# TxPCB_V1-1_LR.net
KiCad netlist of a schematic drawn in EAGLE
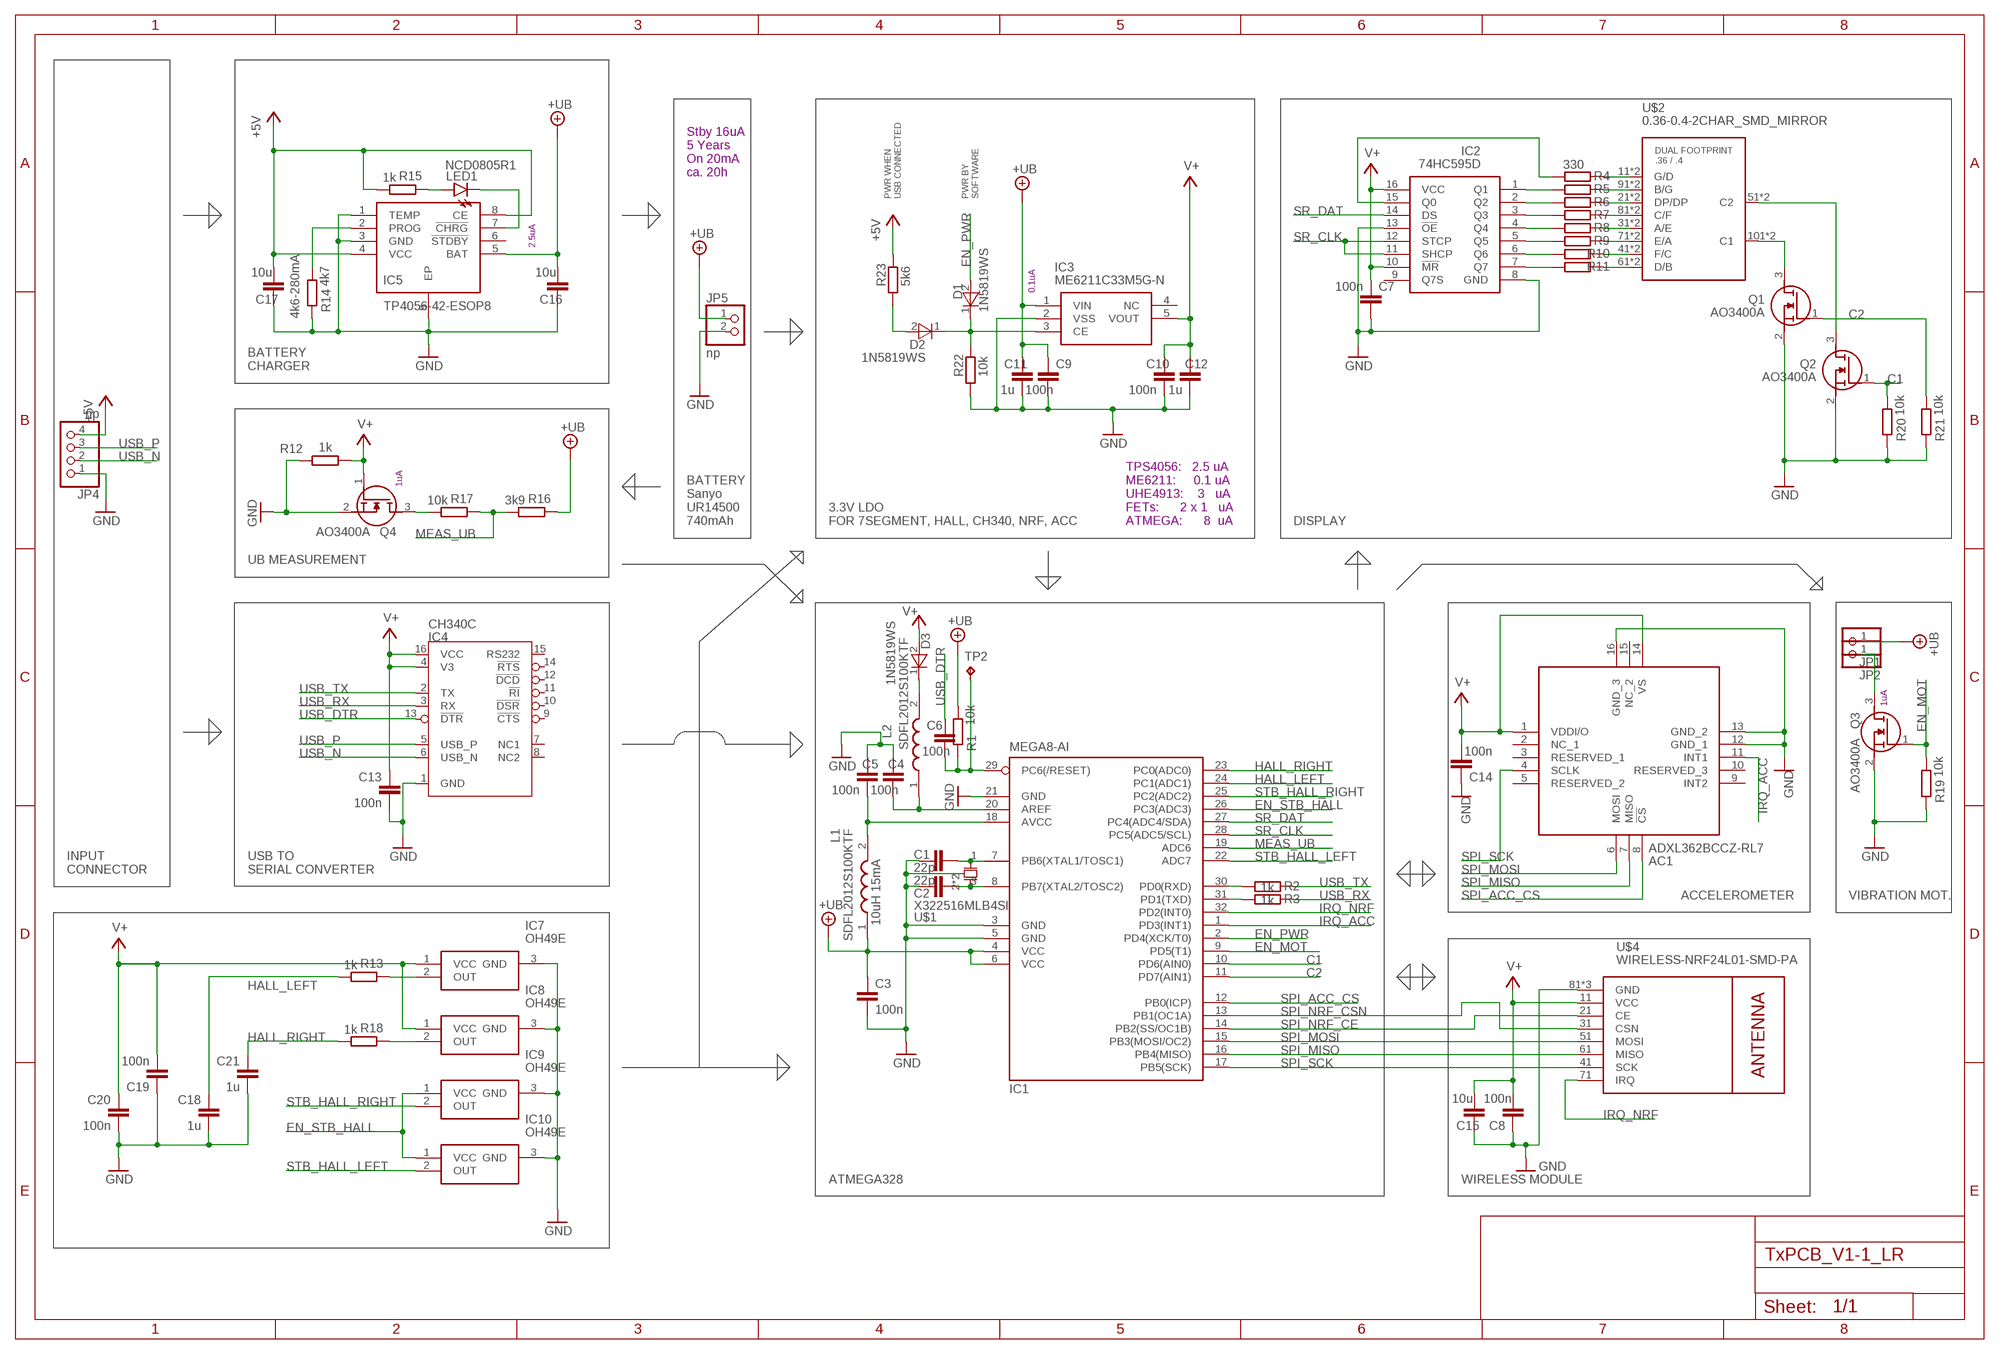
[diagram p0: schematic, sheet 1]

(export (version "E")
  (design (tool "Eeschema 10.0.6"))
  (components
    (comp (ref "AC1")
      (value "ADXL362BCCZ-RL7")
      (footprint "eagle-import:CC-16-4")
      (fields (field (name "MOUSER_PART_NUMBER") "584-ADXL362BCCZ-R7"))
      (libsource (lib "eagle-import") (part "ADXL362BCCZ-RL7"))
    )
    (comp (ref "C1")
      (value "22p")
      (footprint "eagle-import:C0603")
      (libsource (lib "eagle-import") (part "C-EUC0603"))
    )
    (comp (ref "C2")
      (value "22p")
      (footprint "eagle-import:C0603")
      (libsource (lib "eagle-import") (part "C-EUC0603"))
    )
    (comp (ref "C3")
      (value "100n")
      (footprint "eagle-import:C0603")
      (libsource (lib "eagle-import") (part "C-EUC0603"))
    )
    (comp (ref "C4")
      (value "100n")
      (footprint "eagle-import:C0603")
      (libsource (lib "eagle-import") (part "C-EUC0603"))
    )
    (comp (ref "C5")
      (value "100n")
      (footprint "eagle-import:C0603")
      (libsource (lib "eagle-import") (part "C-EUC0603"))
    )
    (comp (ref "C6")
      (value "100n")
      (footprint "eagle-import:C0603")
      (libsource (lib "eagle-import") (part "C-EUC0603"))
    )
    (comp (ref "C7")
      (value "100n")
      (footprint "eagle-import:C0603")
      (libsource (lib "eagle-import") (part "C-EUC0603"))
    )
    (comp (ref "C8")
      (value "100n")
      (footprint "eagle-import:C0603")
      (libsource (lib "eagle-import") (part "C-EUC0603"))
    )
    (comp (ref "C9")
      (value "100n")
      (footprint "eagle-import:C0603")
      (libsource (lib "eagle-import") (part "C-EUC0603"))
    )
    (comp (ref "C10")
      (value "100n")
      (footprint "eagle-import:C0603")
      (libsource (lib "eagle-import") (part "C-EUC0603"))
    )
    (comp (ref "C11")
      (value "1u")
      (footprint "eagle-import:C0603")
      (libsource (lib "eagle-import") (part "C-EUC0603"))
    )
    (comp (ref "C12")
      (value "1u")
      (footprint "eagle-import:C0603")
      (libsource (lib "eagle-import") (part "C-EUC0603"))
    )
    (comp (ref "C13")
      (value "100n")
      (footprint "eagle-import:C0603")
      (libsource (lib "eagle-import") (part "C-EUC0603"))
    )
    (comp (ref "C14")
      (value "100n")
      (footprint "eagle-import:C0603")
      (libsource (lib "eagle-import") (part "C-EUC0603"))
    )
    (comp (ref "C15")
      (value "10u")
      (footprint "eagle-import:C0603")
      (libsource (lib "eagle-import") (part "C-EUC0603"))
    )
    (comp (ref "C16")
      (value "10u")
      (footprint "eagle-import:C0603")
      (libsource (lib "eagle-import") (part "C-EUC0603"))
    )
    (comp (ref "C17")
      (value "10u")
      (footprint "eagle-import:C0603")
      (libsource (lib "eagle-import") (part "C-EUC0603"))
    )
    (comp (ref "C18")
      (value "1u")
      (footprint "eagle-import:C0603")
      (libsource (lib "eagle-import") (part "C-EUC0603"))
    )
    (comp (ref "C19")
      (value "100n")
      (footprint "eagle-import:C0603")
      (libsource (lib "eagle-import") (part "C-EUC0603"))
    )
    (comp (ref "C20")
      (value "100n")
      (footprint "eagle-import:C0603")
      (libsource (lib "eagle-import") (part "C-EUC0603"))
    )
    (comp (ref "C21")
      (value "1u")
      (footprint "eagle-import:C0603")
      (libsource (lib "eagle-import") (part "C-EUC0603"))
    )
    (comp (ref "D1")
      (value "1N5819WS")
      (footprint "eagle-import:SODFL2512X90N")
      (fields
        (field (name "ARROW_PART_NUMBER") "1N4148WS")
        (field (name "MOUSER_PART_NUMBER") "512-1N4148WS")
      )
      (libsource (lib "eagle-import") (part "1N4148WS"))
    )
    (comp (ref "D2")
      (value "1N5819WS")
      (footprint "eagle-import:SODFL2512X90N")
      (fields
        (field (name "ARROW_PART_NUMBER") "1N4148WS")
        (field (name "MOUSER_PART_NUMBER") "512-1N4148WS")
      )
      (libsource (lib "eagle-import") (part "1N4148WS"))
    )
    (comp (ref "D3")
      (value "1N5819WS")
      (footprint "eagle-import:SODFL2512X90N")
      (fields
        (field (name "ARROW_PART_NUMBER") "1N4148WS")
        (field (name "MOUSER_PART_NUMBER") "512-1N4148WS")
      )
      (libsource (lib "eagle-import") (part "1N4148WS"))
    )
    (comp (ref "IC1")
      (value "MEGA8-AI")
      (footprint "eagle-import:TQFP32-08")
      (fields (field (name "MPN") "ATMEGA8-16AU"))
      (libsource (lib "eagle-import") (part "MEGA8-AI"))
    )
    (comp (ref "IC2")
      (value "74HC595D")
      (footprint "eagle-import:SOIC127P600X175-16N")
      (libsource (lib "eagle-import") (part "74HC595D"))
    )
    (comp (ref "IC3")
      (value "ME6211C33M5G-N")
      (footprint "eagle-import:SOT95P282X145-5N")
      (fields (field (name "MANUFACTURER_PART_NUMBER") "ME6211C50M5G"))
      (libsource (lib "eagle-import") (part "ME6211C50M5G"))
    )
    (comp (ref "IC4")
      (value "CH340C")
      (footprint "eagle-import:SOIC16N")
      (libsource (lib "eagle-import") (part "CH340G"))
    )
    (comp (ref "IC5")
      (value "TP4056-42-ESOP8")
      (footprint "eagle-import:SOIC127P600X175-9N")
      (libsource (lib "eagle-import") (part "TP4056-42-ESOP8"))
    )
    (comp (ref "IC7")
      (value "OH49E")
      (footprint "eagle-import:SOT95P237X112-3N")
      (fields
        (field (name "ARROW_PART_NUMBER") "DRV5055A3QDBZR")
        (field (name "MOUSER_PART_NUMBER") "595-DRV5055A3QDBZR")
      )
      (libsource (lib "eagle-import") (part "DRV5055A3QDBZR"))
    )
    (comp (ref "IC8")
      (value "OH49E")
      (footprint "eagle-import:SOT95P237X112-3N")
      (fields
        (field (name "ARROW_PART_NUMBER") "DRV5055A3QDBZR")
        (field (name "MOUSER_PART_NUMBER") "595-DRV5055A3QDBZR")
      )
      (libsource (lib "eagle-import") (part "DRV5055A3QDBZR"))
    )
    (comp (ref "IC9")
      (value "OH49E")
      (footprint "eagle-import:SOT95P237X112-3N")
      (fields
        (field (name "ARROW_PART_NUMBER") "DRV5055A3QDBZR")
        (field (name "MOUSER_PART_NUMBER") "595-DRV5055A3QDBZR")
      )
      (libsource (lib "eagle-import") (part "DRV5055A3QDBZR"))
    )
    (comp (ref "IC10")
      (value "OH49E")
      (footprint "eagle-import:SOT95P237X112-3N")
      (fields
        (field (name "ARROW_PART_NUMBER") "DRV5055A3QDBZR")
        (field (name "MOUSER_PART_NUMBER") "595-DRV5055A3QDBZR")
      )
      (libsource (lib "eagle-import") (part "DRV5055A3QDBZR"))
    )
    (comp (ref "JP1")
      (value "PINHD-1X1")
      (footprint "eagle-import:1X01")
      (libsource (lib "eagle-import") (part "PINHD-1X1"))
    )
    (comp (ref "JP2")
      (value "PINHD-1X1")
      (footprint "eagle-import:1X01")
      (libsource (lib "eagle-import") (part "PINHD-1X1"))
    )
    (comp (ref "JP4")
      (value "np")
      (footprint "eagle-import:1X04")
      (libsource (lib "eagle-import") (part "PINHD-1X4"))
    )
    (comp (ref "JP5")
      (value "np")
      (footprint "eagle-import:1X02")
      (libsource (lib "eagle-import") (part "PINHD-1X2"))
    )
    (comp (ref "L1")
      (value "SDFL2012S100KTF")
      (footprint "eagle-import:INDC2112X105N")
      (fields (field (name "MANUFACTURER_PART_NUMBER") "SDFL2012Q2R7KTF"))
      (libsource (lib "eagle-import") (part "SDFL2012Q2R7KTF"))
    )
    (comp (ref "L2")
      (value "SDFL2012S100KTF")
      (footprint "eagle-import:INDC2112X105N")
      (fields (field (name "MANUFACTURER_PART_NUMBER") "SDFL2012Q2R7KTF"))
      (libsource (lib "eagle-import") (part "SDFL2012Q2R7KTF"))
    )
    (comp (ref "LED1")
      (value "NCD0805R1")
      (footprint "eagle-import:CHIP-LED0805")
      (libsource (lib "eagle-import") (part "LEDCHIP-LED0805"))
    )
    (comp (ref "Q1")
      (value "AO3400A")
      (footprint "eagle-import:SOT95P280X125-3N")
      (libsource (lib "eagle-import") (part "AO3400A"))
    )
    (comp (ref "Q2")
      (value "AO3400A")
      (footprint "eagle-import:SOT95P280X125-3N")
      (libsource (lib "eagle-import") (part "AO3400A"))
    )
    (comp (ref "Q3")
      (value "AO3400A")
      (footprint "eagle-import:SOT95P280X125-3N")
      (libsource (lib "eagle-import") (part "AO3400A"))
    )
    (comp (ref "Q4")
      (value "AO3400A")
      (footprint "eagle-import:SOT95P280X125-3N")
      (libsource (lib "eagle-import") (part "AO3400A"))
    )
    (comp (ref "R1")
      (value "10k")
      (footprint "eagle-import:R0603")
      (libsource (lib "eagle-import") (part "R-EU_R0603"))
    )
    (comp (ref "R2")
      (value "1k")
      (footprint "eagle-import:R0603")
      (libsource (lib "eagle-import") (part "R-EU_R0603"))
    )
    (comp (ref "R3")
      (value "1k")
      (footprint "eagle-import:R0603")
      (libsource (lib "eagle-import") (part "R-EU_R0603"))
    )
    (comp (ref "R4")
      (value "330")
      (footprint "eagle-import:R0603")
      (libsource (lib "eagle-import") (part "R-EU_R0603"))
    )
    (comp (ref "R5")
      (value "330")
      (footprint "eagle-import:R0603")
      (libsource (lib "eagle-import") (part "R-EU_R0603"))
    )
    (comp (ref "R6")
      (value "330")
      (footprint "eagle-import:R0603")
      (libsource (lib "eagle-import") (part "R-EU_R0603"))
    )
    (comp (ref "R7")
      (value "330")
      (footprint "eagle-import:R0603")
      (libsource (lib "eagle-import") (part "R-EU_R0603"))
    )
    (comp (ref "R8")
      (value "330")
      (footprint "eagle-import:R0603")
      (libsource (lib "eagle-import") (part "R-EU_R0603"))
    )
    (comp (ref "R9")
      (value "330")
      (footprint "eagle-import:R0603")
      (libsource (lib "eagle-import") (part "R-EU_R0603"))
    )
    (comp (ref "R10")
      (value "330")
      (footprint "eagle-import:R0603")
      (libsource (lib "eagle-import") (part "R-EU_R0603"))
    )
    (comp (ref "R11")
      (value "330")
      (footprint "eagle-import:R0603")
      (libsource (lib "eagle-import") (part "R-EU_R0603"))
    )
    (comp (ref "R12")
      (value "1k")
      (footprint "eagle-import:R0603")
      (libsource (lib "eagle-import") (part "R-EU_R0603"))
    )
    (comp (ref "R13")
      (value "1k")
      (footprint "eagle-import:R0603")
      (libsource (lib "eagle-import") (part "R-EU_R0603"))
    )
    (comp (ref "R14")
      (value "4k7")
      (footprint "eagle-import:R0603")
      (libsource (lib "eagle-import") (part "R-EU_R0603"))
    )
    (comp (ref "R15")
      (value "1k")
      (footprint "eagle-import:R0603")
      (libsource (lib "eagle-import") (part "R-EU_R0603"))
    )
    (comp (ref "R16")
      (value "3k9")
      (footprint "eagle-import:R0603")
      (libsource (lib "eagle-import") (part "R-EU_R0603"))
    )
    (comp (ref "R17")
      (value "10k")
      (footprint "eagle-import:R0603")
      (libsource (lib "eagle-import") (part "R-EU_R0603"))
    )
    (comp (ref "R18")
      (value "1k")
      (footprint "eagle-import:R0603")
      (libsource (lib "eagle-import") (part "R-EU_R0603"))
    )
    (comp (ref "R19")
      (value "10k")
      (footprint "eagle-import:R0603")
      (libsource (lib "eagle-import") (part "R-EU_R0603"))
    )
    (comp (ref "R20")
      (value "10k")
      (footprint "eagle-import:R0603")
      (libsource (lib "eagle-import") (part "R-EU_R0603"))
    )
    (comp (ref "R21")
      (value "10k")
      (footprint "eagle-import:R0603")
      (libsource (lib "eagle-import") (part "R-EU_R0603"))
    )
    (comp (ref "R22")
      (value "10k")
      (footprint "eagle-import:R0603")
      (libsource (lib "eagle-import") (part "R-EU_R0603"))
    )
    (comp (ref "R23")
      (value "5k6")
      (footprint "eagle-import:R0603")
      (libsource (lib "eagle-import") (part "R-EU_R0603"))
    )
    (comp (ref "TP2")
      (value "TPB1,27")
      (footprint "eagle-import:B1,27")
      (libsource (lib "eagle-import") (part "TPB1,27"))
    )
    (comp (ref "U$1")
      (value "X322516MLB4SI")
      (footprint "eagle-import:X322516MLB4SI")
      (libsource (lib "eagle-import") (part "X322516_BETTER"))
    )
    (comp (ref "U$2")
      (value "0.36-0.4-2CHAR_SMD_MIRROR")
      (footprint "eagle-import:COMBO-036-04_SMD")
      (libsource (lib "eagle-import") (part "0.36-0.4-2CHAR_SMD_MIRROR"))
    )
    (comp (ref "U$4")
      (value "WIRELESS-NRF24L01-SMD-PA")
      (footprint "eagle-import:WIRELESS-NRF24L01_SMD_PA")
      (libsource (lib "eagle-import") (part "WIRELESS-NRF24L01-SMD-PA"))
    )
  )
  (nets
    (net (code "1") (name "+5V") (class "Default")
      (node (ref "C17") (pin "1") (pinfunction "1_1") (pintype "passive"))
      (node (ref "IC5") (pin "4") (pinfunction "VCC_4") (pintype "bidirectional"))
      (node (ref "IC5") (pin "8") (pinfunction "CE_8") (pintype "bidirectional"))
      (node (ref "JP4") (pin "4") (pinfunction "4_4") (pintype "passive"))
      (node (ref "R15") (pin "2") (pinfunction "2_2") (pintype "passive"))
      (node (ref "R23") (pin "2") (pinfunction "2_2") (pintype "passive"))
    )
    (net (code "2") (name "+UB") (class "Default")
      (node (ref "C11") (pin "1") (pinfunction "1_1") (pintype "passive"))
      (node (ref "C16") (pin "1") (pinfunction "1_1") (pintype "passive"))
      (node (ref "C3") (pin "1") (pinfunction "1_1") (pintype "passive"))
      (node (ref "C9") (pin "1") (pinfunction "1_1") (pintype "passive"))
      (node (ref "IC1") (pin "4") (pinfunction "VCC_4") (pintype "power_in"))
      (node (ref "IC1") (pin "6") (pinfunction "VCC_6") (pintype "power_in"))
      (node (ref "IC3") (pin "1") (pinfunction "VIN_1") (pintype "bidirectional"))
      (node (ref "IC5") (pin "5") (pinfunction "BAT_5") (pintype "bidirectional"))
      (node (ref "JP1") (pin "1") (pinfunction "1_1") (pintype "passive"))
      (node (ref "JP5") (pin "1") (pinfunction "1_1") (pintype "passive"))
      (node (ref "L1") (pin "1") (pinfunction "1_1") (pintype "bidirectional"))
      (node (ref "R1") (pin "2") (pinfunction "2_2") (pintype "passive"))
      (node (ref "R16") (pin "1") (pinfunction "1_1") (pintype "passive"))
    )
    (net (code "3") (name "/C1") (class "Default")
      (node (ref "IC1") (pin "10") (pinfunction "PD6(AIN0)_10") (pintype "bidirectional"))
      (node (ref "Q2") (pin "1") (pinfunction "G_1") (pintype "bidirectional"))
      (node (ref "R20") (pin "2") (pinfunction "2_2") (pintype "passive"))
    )
    (net (code "4") (name "/C2") (class "Default")
      (node (ref "IC1") (pin "11") (pinfunction "PD7(AIN1)_11") (pintype "bidirectional"))
      (node (ref "Q1") (pin "1") (pinfunction "G_1") (pintype "bidirectional"))
      (node (ref "R21") (pin "2") (pinfunction "2_2") (pintype "passive"))
    )
    (net (code "5") (name "/EN_MOT") (class "Default")
      (node (ref "IC1") (pin "9") (pinfunction "PD5(T1)_9") (pintype "bidirectional"))
      (node (ref "Q3") (pin "1") (pinfunction "G_1") (pintype "bidirectional"))
      (node (ref "R19") (pin "2") (pinfunction "2_2") (pintype "passive"))
    )
    (net (code "6") (name "/EN_PWR") (class "Default")
      (node (ref "D1") (pin "2") (pinfunction "A_2") (pintype "bidirectional"))
      (node (ref "IC1") (pin "2") (pinfunction "PD4(XCK/T0)_2") (pintype "bidirectional"))
    )
    (net (code "7") (name "/EN_STB_HALL") (class "Default")
      (node (ref "IC1") (pin "26") (pinfunction "PC3(ADC3)_26") (pintype "bidirectional"))
      (node (ref "IC10") (pin "1") (pinfunction "VCC_1") (pintype "bidirectional"))
      (node (ref "IC9") (pin "1") (pinfunction "VCC_1") (pintype "bidirectional"))
    )
    (net (code "8") (name "/HALL_LEFT") (class "Default")
      (node (ref "C18") (pin "1") (pinfunction "1_1") (pintype "passive"))
      (node (ref "IC1") (pin "24") (pinfunction "PC1(ADC1)_24") (pintype "bidirectional"))
      (node (ref "R13") (pin "2") (pinfunction "2_2") (pintype "passive"))
    )
    (net (code "9") (name "/HALL_RIGHT") (class "Default")
      (node (ref "C21") (pin "1") (pinfunction "1_1") (pintype "passive"))
      (node (ref "IC1") (pin "23") (pinfunction "PC0(ADC0)_23") (pintype "bidirectional"))
      (node (ref "R18") (pin "2") (pinfunction "2_2") (pintype "passive"))
    )
    (net (code "10") (name "/IRQ_ACC") (class "Default")
      (node (ref "AC1") (pin "11") (pinfunction "INT1_11") (pintype "input"))
      (node (ref "IC1") (pin "1") (pinfunction "PD3(INT1)_1") (pintype "bidirectional"))
    )
    (net (code "11") (name "/IRQ_NRF") (class "Default")
      (node (ref "IC1") (pin "32") (pinfunction "PD2(INT0)_32") (pintype "bidirectional"))
      (node (ref "U$4") (pin "71") (pinfunction "IRQ_71") (pintype "bidirectional"))
    )
    (net (code "12") (name "/MEAS_UB") (class "Default")
      (node (ref "IC1") (pin "19") (pinfunction "ADC6_19") (pintype "bidirectional"))
      (node (ref "R16") (pin "2") (pinfunction "2_2") (pintype "passive"))
      (node (ref "R17") (pin "1") (pinfunction "1_1") (pintype "passive"))
    )
    (net (code "13") (name "/SPI_ACC_CS") (class "Default")
      (node (ref "AC1") (pin "8") (pinfunction "~{CS}_8") (pintype "input"))
      (node (ref "IC1") (pin "12") (pinfunction "PB0(ICP)_12") (pintype "bidirectional"))
    )
    (net (code "14") (name "/SPI_MISO") (class "Default")
      (node (ref "AC1") (pin "7") (pinfunction "MISO_7") (pintype "bidirectional"))
      (node (ref "IC1") (pin "16") (pinfunction "PB4(MISO)_16") (pintype "bidirectional"))
      (node (ref "U$4") (pin "61") (pinfunction "MISO_61") (pintype "bidirectional"))
    )
    (net (code "15") (name "/SPI_MOSI") (class "Default")
      (node (ref "AC1") (pin "6") (pinfunction "MOSI_6") (pintype "bidirectional"))
      (node (ref "IC1") (pin "15") (pinfunction "PB3(MOSI/OC2)_15") (pintype "bidirectional"))
      (node (ref "U$4") (pin "51") (pinfunction "MOSI_51") (pintype "bidirectional"))
    )
    (net (code "16") (name "/SPI_NRF_CE") (class "Default")
      (node (ref "IC1") (pin "14") (pinfunction "PB2(SS/OC1B)_14") (pintype "bidirectional"))
      (node (ref "U$4") (pin "21") (pinfunction "CE_21") (pintype "bidirectional"))
    )
    (net (code "17") (name "/SPI_NRF_CSN") (class "Default")
      (node (ref "IC1") (pin "13") (pinfunction "PB1(OC1A)_13") (pintype "bidirectional"))
      (node (ref "U$4") (pin "31") (pinfunction "CSN_31") (pintype "bidirectional"))
    )
    (net (code "18") (name "/SPI_SCK") (class "Default")
      (node (ref "AC1") (pin "4") (pinfunction "SCLK_4") (pintype "input"))
      (node (ref "IC1") (pin "17") (pinfunction "PB5(SCK)_17") (pintype "bidirectional"))
      (node (ref "U$4") (pin "41") (pinfunction "SCK_41") (pintype "bidirectional"))
    )
    (net (code "19") (name "/SR_CLK") (class "Default")
      (node (ref "IC1") (pin "28") (pinfunction "PC5(ADC5/SCL)_28") (pintype "bidirectional"))
      (node (ref "IC2") (pin "11") (pinfunction "SHCP_11") (pintype "bidirectional"))
      (node (ref "IC2") (pin "12") (pinfunction "STCP_12") (pintype "bidirectional"))
    )
    (net (code "20") (name "/SR_DAT") (class "Default")
      (node (ref "IC1") (pin "27") (pinfunction "PC4(ADC4/SDA)_27") (pintype "bidirectional"))
      (node (ref "IC2") (pin "14") (pinfunction "DS_14") (pintype "bidirectional"))
    )
    (net (code "21") (name "/STB_HALL_LEFT") (class "Default")
      (node (ref "IC1") (pin "22") (pinfunction "ADC7_22") (pintype "bidirectional"))
      (node (ref "IC10") (pin "2") (pinfunction "OUT_2") (pintype "bidirectional"))
    )
    (net (code "22") (name "/STB_HALL_RIGHT") (class "Default")
      (node (ref "IC1") (pin "25") (pinfunction "PC2(ADC2)_25") (pintype "bidirectional"))
      (node (ref "IC9") (pin "2") (pinfunction "OUT_2") (pintype "bidirectional"))
    )
    (net (code "23") (name "/USB_DTR") (class "Default")
      (node (ref "C6") (pin "1") (pinfunction "1_1") (pintype "passive"))
      (node (ref "IC4") (pin "13") (pinfunction "~{DTR}_13") (pintype "output"))
    )
    (net (code "24") (name "/USB_N") (class "Default")
      (node (ref "IC4") (pin "6") (pinfunction "USB_N_6") (pintype "bidirectional"))
      (node (ref "JP4") (pin "2") (pinfunction "2_2") (pintype "passive"))
    )
    (net (code "25") (name "/USB_P") (class "Default")
      (node (ref "IC4") (pin "5") (pinfunction "USB_P_5") (pintype "bidirectional"))
      (node (ref "JP4") (pin "3") (pinfunction "3_3") (pintype "passive"))
    )
    (net (code "26") (name "/USB_RX") (class "Default")
      (node (ref "IC4") (pin "3") (pinfunction "RX_3") (pintype "input"))
      (node (ref "R3") (pin "1") (pinfunction "1_1") (pintype "passive"))
    )
    (net (code "27") (name "/USB_TX") (class "Default")
      (node (ref "IC4") (pin "2") (pinfunction "TX_2") (pintype "output"))
      (node (ref "R2") (pin "1") (pinfunction "1_1") (pintype "passive"))
    )
    (net (code "28") (name "GND") (class "Default")
      (node (ref "AC1") (pin "12") (pinfunction "GND_1_12") (pintype "power_in"))
      (node (ref "AC1") (pin "13") (pinfunction "GND_2_13") (pintype "power_in"))
      (node (ref "AC1") (pin "16") (pinfunction "GND_3_16") (pintype "power_in"))
      (node (ref "C1") (pin "2") (pinfunction "2_2") (pintype "passive"))
      (node (ref "C10") (pin "2") (pinfunction "2_2") (pintype "passive"))
      (node (ref "C11") (pin "2") (pinfunction "2_2") (pintype "passive"))
      (node (ref "C12") (pin "2") (pinfunction "2_2") (pintype "passive"))
      (node (ref "C13") (pin "2") (pinfunction "2_2") (pintype "passive"))
      (node (ref "C14") (pin "1") (pinfunction "1_1") (pintype "passive"))
      (node (ref "C15") (pin "2") (pinfunction "2_2") (pintype "passive"))
      (node (ref "C16") (pin "2") (pinfunction "2_2") (pintype "passive"))
      (node (ref "C17") (pin "2") (pinfunction "2_2") (pintype "passive"))
      (node (ref "C18") (pin "2") (pinfunction "2_2") (pintype "passive"))
      (node (ref "C19") (pin "1") (pinfunction "1_1") (pintype "passive"))
      (node (ref "C2") (pin "2") (pinfunction "2_2") (pintype "passive"))
      (node (ref "C20") (pin "2") (pinfunction "2_2") (pintype "passive"))
      (node (ref "C21") (pin "2") (pinfunction "2_2") (pintype "passive"))
      (node (ref "C3") (pin "2") (pinfunction "2_2") (pintype "passive"))
      (node (ref "C4") (pin "1") (pinfunction "1_1") (pintype "passive"))
      (node (ref "C5") (pin "1") (pinfunction "1_1") (pintype "passive"))
      (node (ref "C7") (pin "2") (pinfunction "2_2") (pintype "passive"))
      (node (ref "C8") (pin "1") (pinfunction "1_1") (pintype "passive"))
      (node (ref "C9") (pin "2") (pinfunction "2_2") (pintype "passive"))
      (node (ref "IC1") (pin "21") (pinfunction "GND_21") (pintype "power_in"))
      (node (ref "IC1") (pin "3") (pinfunction "GND_3") (pintype "power_in"))
      (node (ref "IC1") (pin "5") (pinfunction "GND_5") (pintype "power_in"))
      (node (ref "IC10") (pin "3") (pinfunction "GND_3") (pintype "bidirectional"))
      (node (ref "IC2") (pin "13") (pinfunction "~{OE}_13") (pintype "bidirectional"))
      (node (ref "IC2") (pin "8") (pinfunction "GND_8") (pintype "bidirectional"))
      (node (ref "IC3") (pin "2") (pinfunction "VSS_2") (pintype "bidirectional"))
      (node (ref "IC4") (pin "1") (pinfunction "GND_1") (pintype "input"))
      (node (ref "IC5") (pin "1") (pinfunction "TEMP_1") (pintype "bidirectional"))
      (node (ref "IC5") (pin "3") (pinfunction "GND_3") (pintype "bidirectional"))
      (node (ref "IC5") (pin "9") (pinfunction "EP_9") (pintype "bidirectional"))
      (node (ref "IC7") (pin "3") (pinfunction "GND_3") (pintype "bidirectional"))
      (node (ref "IC8") (pin "3") (pinfunction "GND_3") (pintype "bidirectional"))
      (node (ref "IC9") (pin "3") (pinfunction "GND_3") (pintype "bidirectional"))
      (node (ref "JP4") (pin "1") (pinfunction "1_1") (pintype "passive"))
      (node (ref "JP5") (pin "2") (pinfunction "2_2") (pintype "passive"))
      (node (ref "Q1") (pin "2") (pinfunction "S_2") (pintype "bidirectional"))
      (node (ref "Q2") (pin "2") (pinfunction "S_2") (pintype "bidirectional"))
      (node (ref "Q3") (pin "2") (pinfunction "S_2") (pintype "bidirectional"))
      (node (ref "Q4") (pin "2") (pinfunction "S_2") (pintype "bidirectional"))
      (node (ref "R12") (pin "1") (pinfunction "1_1") (pintype "passive"))
      (node (ref "R14") (pin "1") (pinfunction "1_1") (pintype "passive"))
      (node (ref "R19") (pin "1") (pinfunction "1_1") (pintype "passive"))
      (node (ref "R20") (pin "1") (pinfunction "1_1") (pintype "passive"))
      (node (ref "R21") (pin "1") (pinfunction "1_1") (pintype "passive"))
      (node (ref "R22") (pin "1") (pinfunction "1_1") (pintype "passive"))
      (node (ref "U$1") (pin "2") (pinfunction "G_2") (pintype "bidirectional"))
      (node (ref "U$1") (pin "4") (pinfunction "G_4") (pintype "bidirectional"))
      (node (ref "U$4") (pin "81") (pinfunction "GND_81") (pintype "power_in"))
      (node (ref "U$4") (pin "P1") (pinfunction "GND_P1") (pintype "power_in"))
      (node (ref "U$4") (pin "P2") (pinfunction "GND_P2") (pintype "power_in"))
    )
    (net (code "29") (name "Net-(D1-K)") (class "Default")
      (node (ref "D1") (pin "1") (pinfunction "K_1") (pintype "bidirectional"))
      (node (ref "D2") (pin "1") (pinfunction "K_1") (pintype "bidirectional"))
      (node (ref "IC3") (pin "3") (pinfunction "CE_3") (pintype "bidirectional"))
      (node (ref "R22") (pin "2") (pinfunction "2_2") (pintype "passive"))
    )
    (net (code "30") (name "Net-(D2-A)") (class "Default")
      (node (ref "D2") (pin "2") (pinfunction "A_2") (pintype "bidirectional"))
      (node (ref "R23") (pin "1") (pinfunction "1_1") (pintype "passive"))
    )
    (net (code "31") (name "Net-(D3-K)") (class "Default")
      (node (ref "D3") (pin "1") (pinfunction "K_1") (pintype "bidirectional"))
      (node (ref "L2") (pin "2") (pinfunction "2_2") (pintype "bidirectional"))
    )
    (net (code "32") (name "Net-(IC1-AREF)") (class "Default")
      (node (ref "C4") (pin "2") (pinfunction "2_2") (pintype "passive"))
      (node (ref "IC1") (pin "20") (pinfunction "AREF_20") (pintype "passive"))
      (node (ref "L2") (pin "1") (pinfunction "1_1") (pintype "bidirectional"))
    )
    (net (code "33") (name "Net-(IC1-AVCC)") (class "Default")
      (node (ref "C5") (pin "2") (pinfunction "2_2") (pintype "passive"))
      (node (ref "IC1") (pin "18") (pinfunction "AVCC_18") (pintype "power_in"))
      (node (ref "L1") (pin "2") (pinfunction "2_2") (pintype "bidirectional"))
    )
    (net (code "34") (name "Net-(IC1-PB6(XTAL1{slash}TOSC1))") (class "Default")
      (node (ref "C1") (pin "1") (pinfunction "1_1") (pintype "passive"))
      (node (ref "IC1") (pin "7") (pinfunction "PB6(XTAL1/TOSC1)_7") (pintype "bidirectional"))
      (node (ref "U$1") (pin "1") (pinfunction "X1_1") (pintype "bidirectional"))
    )
    (net (code "35") (name "Net-(IC1-PB7(XTAL2{slash}TOSC2))") (class "Default")
      (node (ref "C2") (pin "1") (pinfunction "1_1") (pintype "passive"))
      (node (ref "IC1") (pin "8") (pinfunction "PB7(XTAL2/TOSC2)_8") (pintype "bidirectional"))
      (node (ref "U$1") (pin "3") (pinfunction "X2_3") (pintype "bidirectional"))
    )
    (net (code "36") (name "Net-(IC1-PC6({slash}RESET))") (class "Default")
      (node (ref "C6") (pin "2") (pinfunction "2_2") (pintype "passive"))
      (node (ref "IC1") (pin "29") (pinfunction "PC6(/RESET)_29") (pintype "bidirectional"))
      (node (ref "R1") (pin "1") (pinfunction "1_1") (pintype "passive"))
      (node (ref "TP2") (pin "TP") (pinfunction "TP_TP") (pintype "input"))
    )
    (net (code "37") (name "Net-(IC1-PD0(RXD))") (class "Default")
      (node (ref "IC1") (pin "30") (pinfunction "PD0(RXD)_30") (pintype "bidirectional"))
      (node (ref "R2") (pin "2") (pinfunction "2_2") (pintype "passive"))
    )
    (net (code "38") (name "Net-(IC1-PD1(TXD))") (class "Default")
      (node (ref "IC1") (pin "31") (pinfunction "PD1(TXD)_31") (pintype "bidirectional"))
      (node (ref "R3") (pin "2") (pinfunction "2_2") (pintype "passive"))
    )
    (net (code "39") (name "Net-(IC2-Q0)") (class "Default")
      (node (ref "IC2") (pin "15") (pinfunction "Q0_15") (pintype "bidirectional"))
      (node (ref "R4") (pin "2") (pinfunction "2_2") (pintype "passive"))
    )
    (net (code "40") (name "Net-(IC2-Q1)") (class "Default")
      (node (ref "IC2") (pin "1") (pinfunction "Q1_1") (pintype "bidirectional"))
      (node (ref "R5") (pin "2") (pinfunction "2_2") (pintype "passive"))
    )
    (net (code "41") (name "Net-(IC2-Q2)") (class "Default")
      (node (ref "IC2") (pin "2") (pinfunction "Q2_2") (pintype "bidirectional"))
      (node (ref "R6") (pin "2") (pinfunction "2_2") (pintype "passive"))
    )
    (net (code "42") (name "Net-(IC2-Q3)") (class "Default")
      (node (ref "IC2") (pin "3") (pinfunction "Q3_3") (pintype "bidirectional"))
      (node (ref "R7") (pin "2") (pinfunction "2_2") (pintype "passive"))
    )
    (net (code "43") (name "Net-(IC2-Q4)") (class "Default")
      (node (ref "IC2") (pin "4") (pinfunction "Q4_4") (pintype "bidirectional"))
      (node (ref "R8") (pin "2") (pinfunction "2_2") (pintype "passive"))
    )
    (net (code "44") (name "Net-(IC2-Q5)") (class "Default")
      (node (ref "IC2") (pin "5") (pinfunction "Q5_5") (pintype "bidirectional"))
      (node (ref "R9") (pin "2") (pinfunction "2_2") (pintype "passive"))
    )
    (net (code "45") (name "Net-(IC2-Q6)") (class "Default")
      (node (ref "IC2") (pin "6") (pinfunction "Q6_6") (pintype "bidirectional"))
      (node (ref "R10") (pin "2") (pinfunction "2_2") (pintype "passive"))
    )
    (net (code "46") (name "Net-(IC2-Q7)") (class "Default")
      (node (ref "IC2") (pin "7") (pinfunction "Q7_7") (pintype "bidirectional"))
      (node (ref "R11") (pin "2") (pinfunction "2_2") (pintype "passive"))
    )
    (net (code "47") (name "Net-(IC5-PROG)") (class "Default")
      (node (ref "IC5") (pin "2") (pinfunction "PROG_2") (pintype "bidirectional"))
      (node (ref "R14") (pin "2") (pinfunction "2_2") (pintype "passive"))
    )
    (net (code "48") (name "Net-(IC5-~{CHRG})") (class "Default")
      (node (ref "IC5") (pin "7") (pinfunction "~{CHRG}_7") (pintype "bidirectional"))
      (node (ref "LED1") (pin "C") (pinfunction "C_C") (pintype "passive"))
    )
    (net (code "49") (name "Net-(IC7-OUT)") (class "Default")
      (node (ref "IC7") (pin "2") (pinfunction "OUT_2") (pintype "bidirectional"))
      (node (ref "R13") (pin "1") (pinfunction "1_1") (pintype "passive"))
    )
    (net (code "50") (name "Net-(IC8-OUT)") (class "Default")
      (node (ref "IC8") (pin "2") (pinfunction "OUT_2") (pintype "bidirectional"))
      (node (ref "R18") (pin "1") (pinfunction "1_1") (pintype "passive"))
    )
    (net (code "51") (name "Net-(LED1-PadA)") (class "Default")
      (node (ref "LED1") (pin "A") (pinfunction "A_A") (pintype "passive"))
      (node (ref "R15") (pin "1") (pinfunction "1_1") (pintype "passive"))
    )
    (net (code "52") (name "Net-(Q1-D)") (class "Default")
      (node (ref "Q1") (pin "3") (pinfunction "D_3") (pintype "bidirectional"))
      (node (ref "U$2") (pin "101") (pinfunction "C1_101") (pintype "bidirectional"))
      (node (ref "U$2") (pin "102") (pinfunction "C1_102") (pintype "bidirectional"))
    )
    (net (code "53") (name "Net-(Q2-D)") (class "Default")
      (node (ref "Q2") (pin "3") (pinfunction "D_3") (pintype "bidirectional"))
      (node (ref "U$2") (pin "51") (pinfunction "C2_51") (pintype "bidirectional"))
      (node (ref "U$2") (pin "52") (pinfunction "C2_52") (pintype "bidirectional"))
    )
    (net (code "54") (name "Net-(Q3-D)") (class "Default")
      (node (ref "JP2") (pin "1") (pinfunction "1_1") (pintype "passive"))
      (node (ref "Q3") (pin "3") (pinfunction "D_3") (pintype "bidirectional"))
    )
    (net (code "55") (name "Net-(Q4-D)") (class "Default")
      (node (ref "Q4") (pin "3") (pinfunction "D_3") (pintype "bidirectional"))
      (node (ref "R17") (pin "2") (pinfunction "2_2") (pintype "passive"))
    )
    (net (code "56") (name "Net-(R4-Pad1)") (class "Default")
      (node (ref "R4") (pin "1") (pinfunction "1_1") (pintype "passive"))
      (node (ref "U$2") (pin "11") (pinfunction "G/D_11") (pintype "bidirectional"))
      (node (ref "U$2") (pin "12") (pinfunction "G/D_12") (pintype "bidirectional"))
    )
    (net (code "57") (name "Net-(R5-Pad1)") (class "Default")
      (node (ref "R5") (pin "1") (pinfunction "1_1") (pintype "passive"))
      (node (ref "U$2") (pin "91") (pinfunction "B/G_91") (pintype "bidirectional"))
      (node (ref "U$2") (pin "92") (pinfunction "B/G_92") (pintype "bidirectional"))
    )
    (net (code "58") (name "Net-(R6-Pad1)") (class "Default")
      (node (ref "R6") (pin "1") (pinfunction "1_1") (pintype "passive"))
      (node (ref "U$2") (pin "21") (pinfunction "DP/DP_21") (pintype "bidirectional"))
      (node (ref "U$2") (pin "22") (pinfunction "DP/DP_22") (pintype "bidirectional"))
    )
    (net (code "59") (name "Net-(R7-Pad1)") (class "Default")
      (node (ref "R7") (pin "1") (pinfunction "1_1") (pintype "passive"))
      (node (ref "U$2") (pin "81") (pinfunction "C/F_81") (pintype "bidirectional"))
      (node (ref "U$2") (pin "82") (pinfunction "C/F_82") (pintype "bidirectional"))
    )
    (net (code "60") (name "Net-(R8-Pad1)") (class "Default")
      (node (ref "R8") (pin "1") (pinfunction "1_1") (pintype "passive"))
      (node (ref "U$2") (pin "31") (pinfunction "A/E_31") (pintype "bidirectional"))
      (node (ref "U$2") (pin "32") (pinfunction "A/E_32") (pintype "bidirectional"))
    )
    (net (code "61") (name "Net-(R9-Pad1)") (class "Default")
      (node (ref "R9") (pin "1") (pinfunction "1_1") (pintype "passive"))
      (node (ref "U$2") (pin "71") (pinfunction "E/A_71") (pintype "bidirectional"))
      (node (ref "U$2") (pin "72") (pinfunction "E/A_72") (pintype "bidirectional"))
    )
    (net (code "62") (name "Net-(R10-Pad1)") (class "Default")
      (node (ref "R10") (pin "1") (pinfunction "1_1") (pintype "passive"))
      (node (ref "U$2") (pin "41") (pinfunction "F/C_41") (pintype "bidirectional"))
      (node (ref "U$2") (pin "42") (pinfunction "F/C_42") (pintype "bidirectional"))
    )
    (net (code "63") (name "Net-(R11-Pad1)") (class "Default")
      (node (ref "R11") (pin "1") (pinfunction "1_1") (pintype "passive"))
      (node (ref "U$2") (pin "61") (pinfunction "D/B_61") (pintype "bidirectional"))
      (node (ref "U$2") (pin "62") (pinfunction "D/B_62") (pintype "bidirectional"))
    )
    (net (code "64") (name "V+") (class "Default")
      (node (ref "AC1") (pin "1") (pinfunction "VDDI/O_1") (pintype "power_in"))
      (node (ref "AC1") (pin "14") (pinfunction "VS_14") (pintype "bidirectional"))
      (node (ref "C10") (pin "1") (pinfunction "1_1") (pintype "passive"))
      (node (ref "C12") (pin "1") (pinfunction "1_1") (pintype "passive"))
      (node (ref "C13") (pin "1") (pinfunction "1_1") (pintype "passive"))
      (node (ref "C14") (pin "2") (pinfunction "2_2") (pintype "passive"))
      (node (ref "C15") (pin "1") (pinfunction "1_1") (pintype "passive"))
      (node (ref "C19") (pin "2") (pinfunction "2_2") (pintype "passive"))
      (node (ref "C20") (pin "1") (pinfunction "1_1") (pintype "passive"))
      (node (ref "C7") (pin "1") (pinfunction "1_1") (pintype "passive"))
      (node (ref "C8") (pin "2") (pinfunction "2_2") (pintype "passive"))
      (node (ref "D3") (pin "2") (pinfunction "A_2") (pintype "bidirectional"))
      (node (ref "IC2") (pin "10") (pinfunction "~{MR}_10") (pintype "bidirectional"))
      (node (ref "IC2") (pin "16") (pinfunction "VCC_16") (pintype "bidirectional"))
      (node (ref "IC3") (pin "5") (pinfunction "VOUT_5") (pintype "bidirectional"))
      (node (ref "IC4") (pin "16") (pinfunction "VCC_16") (pintype "input"))
      (node (ref "IC4") (pin "4") (pinfunction "V3_4") (pintype "output"))
      (node (ref "IC7") (pin "1") (pinfunction "VCC_1") (pintype "bidirectional"))
      (node (ref "IC8") (pin "1") (pinfunction "VCC_1") (pintype "bidirectional"))
      (node (ref "Q4") (pin "1") (pinfunction "G_1") (pintype "bidirectional"))
      (node (ref "R12") (pin "2") (pinfunction "2_2") (pintype "passive"))
      (node (ref "U$4") (pin "11") (pinfunction "VCC_11") (pintype "power_in"))
    )
    (net (code "65") (name "unconnected-(AC1-INT2-Pad9)") (class "Default")
      (node (ref "AC1") (pin "9") (pinfunction "INT2_9") (pintype "input"))
    )
    (net (code "66") (name "unconnected-(AC1-NC_1-Pad2)") (class "Default")
      (node (ref "AC1") (pin "2") (pinfunction "NC_1_2") (pintype "bidirectional"))
    )
    (net (code "67") (name "unconnected-(AC1-NC_2-Pad15)") (class "Default")
      (node (ref "AC1") (pin "15") (pinfunction "NC_2_15") (pintype "bidirectional"))
    )
    (net (code "68") (name "unconnected-(AC1-RESERVED_1-Pad3)") (class "Default")
      (node (ref "AC1") (pin "3") (pinfunction "RESERVED_1_3") (pintype "bidirectional"))
    )
    (net (code "69") (name "unconnected-(AC1-RESERVED_2-Pad5)") (class "Default")
      (node (ref "AC1") (pin "5") (pinfunction "RESERVED_2_5") (pintype "bidirectional"))
    )
    (net (code "70") (name "unconnected-(AC1-RESERVED_3-Pad10)") (class "Default")
      (node (ref "AC1") (pin "10") (pinfunction "RESERVED_3_10") (pintype "bidirectional"))
    )
    (net (code "71") (name "unconnected-(IC2-Q7S-Pad9)") (class "Default")
      (node (ref "IC2") (pin "9") (pinfunction "Q7S_9") (pintype "bidirectional"))
    )
    (net (code "72") (name "unconnected-(IC3-NC-Pad4)") (class "Default")
      (node (ref "IC3") (pin "4") (pinfunction "NC_4") (pintype "no_connect"))
    )
    (net (code "73") (name "unconnected-(IC4-NC1-Pad7)") (class "Default")
      (node (ref "IC4") (pin "7") (pinfunction "NC1_7") (pintype "no_connect"))
    )
    (net (code "74") (name "unconnected-(IC4-NC2-Pad8)") (class "Default")
      (node (ref "IC4") (pin "8") (pinfunction "NC2_8") (pintype "no_connect"))
    )
    (net (code "75") (name "unconnected-(IC4-RS232-Pad15)") (class "Default")
      (node (ref "IC4") (pin "15") (pinfunction "RS232_15") (pintype "input"))
    )
    (net (code "76") (name "unconnected-(IC4-~{CTS}-Pad9)") (class "Default")
      (node (ref "IC4") (pin "9") (pinfunction "~{CTS}_9") (pintype "input"))
    )
    (net (code "77") (name "unconnected-(IC4-~{DCD}-Pad12)") (class "Default")
      (node (ref "IC4") (pin "12") (pinfunction "~{DCD}_12") (pintype "input"))
    )
    (net (code "78") (name "unconnected-(IC4-~{DSR}-Pad10)") (class "Default")
      (node (ref "IC4") (pin "10") (pinfunction "~{DSR}_10") (pintype "input"))
    )
    (net (code "79") (name "unconnected-(IC4-~{RI}-Pad11)") (class "Default")
      (node (ref "IC4") (pin "11") (pinfunction "~{RI}_11") (pintype "input"))
    )
    (net (code "80") (name "unconnected-(IC4-~{RTS}-Pad14)") (class "Default")
      (node (ref "IC4") (pin "14") (pinfunction "~{RTS}_14") (pintype "output"))
    )
    (net (code "81") (name "unconnected-(IC5-~{STDBY}-Pad6)") (class "Default")
      (node (ref "IC5") (pin "6") (pinfunction "~{STDBY}_6") (pintype "bidirectional"))
    )
  )
)
